# record.net
KiCad netlist of a schematic drawn in Altium Designer
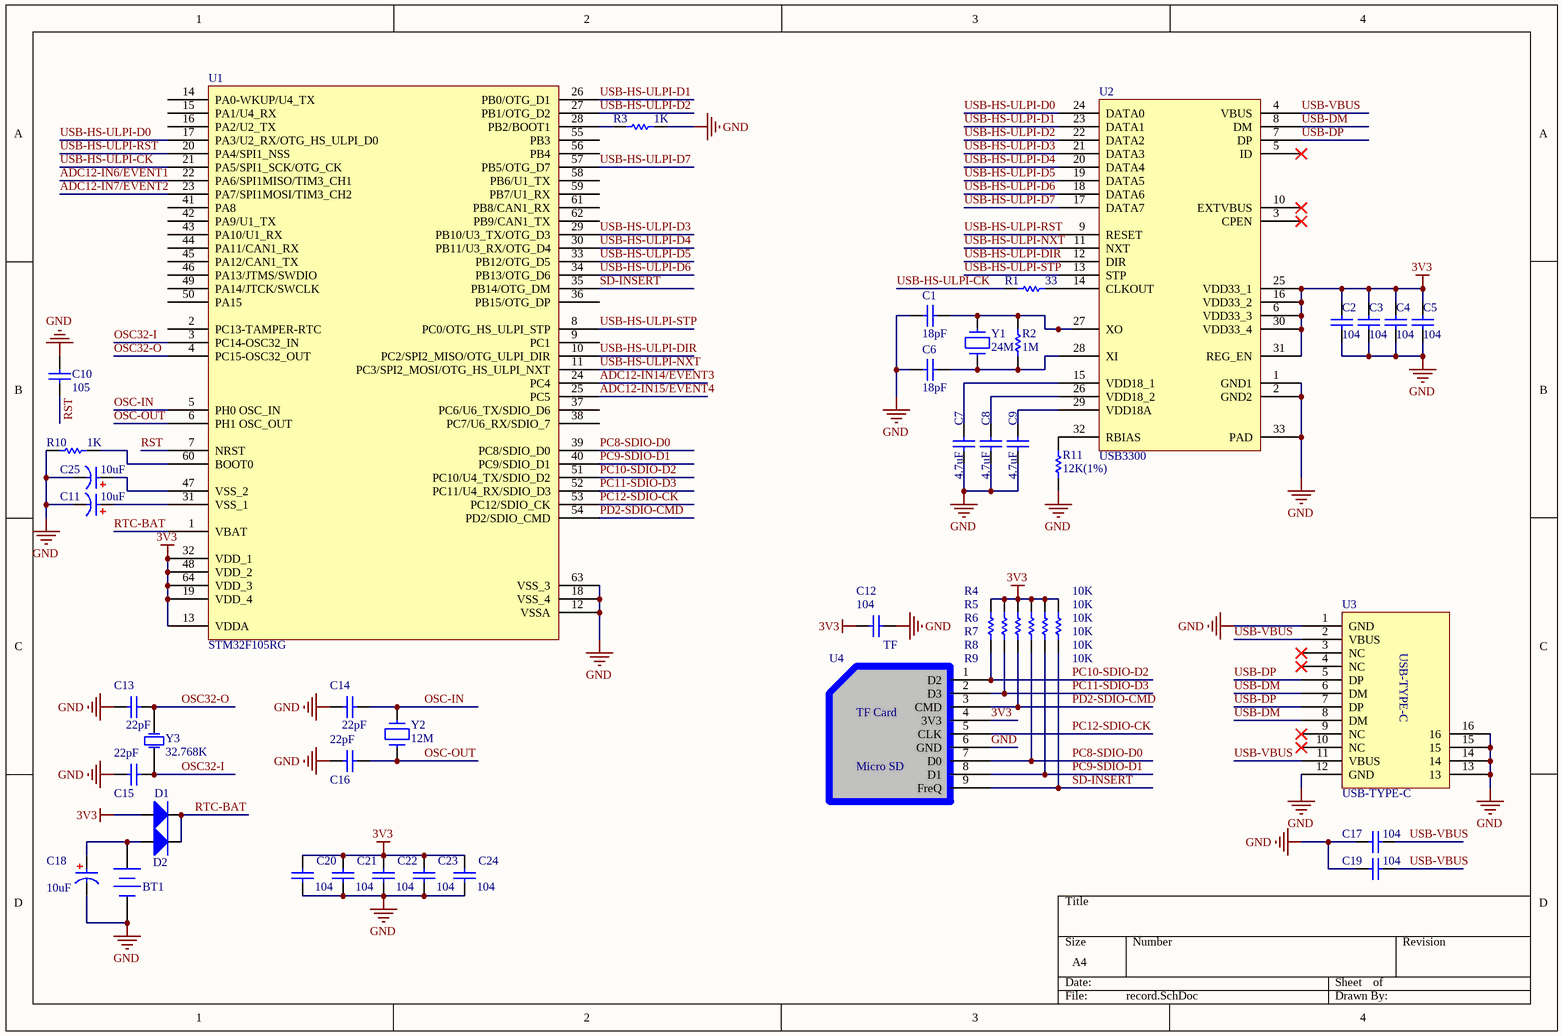
[diagram p0: record.SchDoc]

(export (version "E")
  (design (tool "Eeschema 10.0.6"))
  (components
    (comp (ref "BT1")
      (value "Battery")
      (footprint "BAT1")
      (description "Multicell Battery")
      (fields (field (name "PUBLISHER") "Altium Limited"))
      (libsource (lib "Miscellaneous Devices") (part "Battery"))
    )
    (comp (ref "C1")
      (value "C18pF")
      (footprint "0603R")
      (description "贴片电容")
      (fields (field (name "ALTIUM_UNNAMED_1") "18pF"))
      (libsource (lib "OKmeSchLibrary") (part "C22pF"))
    )
    (comp (ref "C2")
      (value "104")
      (footprint "0603C")
      (fields (field (name "ALTIUM_UNNAMED_1") "104"))
      (libsource (lib "OKmeSchLibrary") (part "C0.1uF"))
    )
    (comp (ref "C3")
      (value "104")
      (footprint "0603C")
      (fields (field (name "ALTIUM_UNNAMED_1") "104"))
      (libsource (lib "OKmeSchLibrary") (part "C0.1uF"))
    )
    (comp (ref "C4")
      (value "104")
      (footprint "0603C")
      (fields (field (name "ALTIUM_UNNAMED_1") "104"))
      (libsource (lib "OKmeSchLibrary") (part "C0.1uF"))
    )
    (comp (ref "C5")
      (value "104")
      (footprint "0603C")
      (fields (field (name "ALTIUM_UNNAMED_1") "104"))
      (libsource (lib "OKmeSchLibrary") (part "C0.1uF"))
    )
    (comp (ref "C6")
      (value "C18pF")
      (footprint "0603R")
      (description "贴片电容")
      (fields (field (name "ALTIUM_UNNAMED_1") "18pF"))
      (libsource (lib "OKmeSchLibrary") (part "C22pF"))
    )
    (comp (ref "C7")
      (value "C4.7uF")
      (footprint "0603R")
      (description "贴片电容")
      (fields (field (name "ALTIUM_UNNAMED_1") "4.7uF"))
      (libsource (lib "OKmeSchLibrary") (part "C22pF"))
    )
    (comp (ref "C8")
      (value "C4.7uF")
      (footprint "0603R")
      (description "贴片电容")
      (fields (field (name "ALTIUM_UNNAMED_1") "4.7uF"))
      (libsource (lib "OKmeSchLibrary") (part "C22pF"))
    )
    (comp (ref "C9")
      (value "C4.7uF")
      (footprint "0603R")
      (description "贴片电容")
      (fields (field (name "ALTIUM_UNNAMED_1") "4.7uF"))
      (libsource (lib "OKmeSchLibrary") (part "C22pF"))
    )
    (comp (ref "C10")
      (value "C1uF")
      (footprint "0603C")
      (fields (field (name "ALTIUM_UNNAMED_1") "105"))
      (libsource (lib "OKmeSchLibrary") (part "C0.1uF"))
    )
    (comp (ref "C11")
      (value "C10uF")
      (footprint "0603C")
      (fields (field (name "ALTIUM_UNNAMED_1") "10uF"))
      (libsource (lib "") (part "C10uF_1"))
    )
    (comp (ref "C12")
      (value "C0.1uF")
      (footprint "0603C")
      (fields (field (name "ALTIUM_UNNAMED_1") "104"))
      (libsource (lib "OKmeSchLibrary") (part "0603C"))
    )
    (comp (ref "C13")
      (value "C22pF")
      (footprint "0603R")
      (fields (field (name "ALTIUM_UNNAMED_1") "22pF"))
      (libsource (lib "OKmeSchLibrary") (part "C22pF"))
    )
    (comp (ref "C14")
      (value "C22pF")
      (footprint "0603R")
      (fields (field (name "ALTIUM_UNNAMED_1") "22pF"))
      (libsource (lib "OKmeSchLibrary") (part "C22pF"))
    )
    (comp (ref "C15")
      (value "C22pF")
      (footprint "0603R")
      (fields (field (name "ALTIUM_UNNAMED_1") "22pF"))
      (libsource (lib "OKmeSchLibrary") (part "C22pF"))
    )
    (comp (ref "C16")
      (value "C22pF")
      (footprint "0603R")
      (fields (field (name "ALTIUM_UNNAMED_1") "22pF"))
      (libsource (lib "OKmeSchLibrary") (part "C22pF"))
    )
    (comp (ref "C17")
      (value "104")
      (footprint "0603C")
      (fields (field (name "ALTIUM_UNNAMED_1") "104"))
      (libsource (lib "OKmeSchLibrary") (part "C0.1uF"))
    )
    (comp (ref "C18")
      (value "C10uF")
      (footprint "0603C")
      (fields (field (name "ALTIUM_UNNAMED_1") "10uF"))
      (libsource (lib "OKmeSchLibrary") (part "C10uF"))
    )
    (comp (ref "C19")
      (value "104")
      (footprint "0603C")
      (fields (field (name "ALTIUM_UNNAMED_1") "104"))
      (libsource (lib "OKmeSchLibrary") (part "C0.1uF"))
    )
    (comp (ref "C20")
      (value "104")
      (footprint "0603C")
      (fields (field (name "ALTIUM_UNNAMED_1") "104"))
      (libsource (lib "OKmeSchLibrary") (part "C0.1uF"))
    )
    (comp (ref "C21")
      (value "104")
      (footprint "0603C")
      (fields (field (name "ALTIUM_UNNAMED_1") "104"))
      (libsource (lib "OKmeSchLibrary") (part "C0.1uF"))
    )
    (comp (ref "C22")
      (value "104")
      (footprint "0603C")
      (fields (field (name "ALTIUM_UNNAMED_1") "104"))
      (libsource (lib "OKmeSchLibrary") (part "C0.1uF"))
    )
    (comp (ref "C23")
      (value "104")
      (footprint "0603C")
      (fields (field (name "ALTIUM_UNNAMED_1") "104"))
      (libsource (lib "OKmeSchLibrary") (part "C0.1uF"))
    )
    (comp (ref "C24")
      (value "104")
      (footprint "0603C")
      (fields (field (name "ALTIUM_UNNAMED_1") "104"))
      (libsource (lib "OKmeSchLibrary") (part "C0.1uF"))
    )
    (comp (ref "C25")
      (value "C10uF")
      (footprint "0603C")
      (fields (field (name "ALTIUM_UNNAMED_1") "10uF"))
      (libsource (lib "") (part "C10uF_1"))
    )
    (comp (ref "D1") (value "1N5822") (footprint "1206") (libsource (lib "OKmeSchLibrary") (part "1N5822")))
    (comp (ref "D2") (value "1N5822") (footprint "1206") (libsource (lib "OKmeSchLibrary") (part "1N5822")))
    (comp (ref "R1")
      (value "R33")
      (footprint "0603R")
      (fields (field (name "ALTIUM_UNNAMED_1") "33"))
      (libsource (lib "OKmeSchLibrary") (part "R22"))
    )
    (comp (ref "R2")
      (value "R1M")
      (footprint "0603R")
      (fields (field (name "ALTIUM_UNNAMED_1") "1M"))
      (libsource (lib "OKmeSchLibrary") (part "R1M"))
    )
    (comp (ref "R3")
      (value "R1K")
      (footprint "0603R")
      (fields (field (name "ALTIUM_UNNAMED_1") "1K"))
      (libsource (lib "OKmeSchLibrary") (part "R10K"))
    )
    (comp (ref "R4")
      (value "R10K")
      (footprint "0603R")
      (fields (field (name "ALTIUM_UNNAMED_1") "10K"))
      (libsource (lib "OKmeSchLibrary") (part "R10K"))
    )
    (comp (ref "R5")
      (value "R10K")
      (footprint "0603R")
      (fields (field (name "ALTIUM_UNNAMED_1") "10K"))
      (libsource (lib "OKmeSchLibrary") (part "R10K"))
    )
    (comp (ref "R6")
      (value "R10K")
      (footprint "0603R")
      (fields (field (name "ALTIUM_UNNAMED_1") "10K"))
      (libsource (lib "OKmeSchLibrary") (part "R10K"))
    )
    (comp (ref "R7")
      (value "R10K")
      (footprint "0603R")
      (fields (field (name "ALTIUM_UNNAMED_1") "10K"))
      (libsource (lib "OKmeSchLibrary") (part "R10K"))
    )
    (comp (ref "R8")
      (value "R10K")
      (footprint "0603R")
      (fields (field (name "ALTIUM_UNNAMED_1") "10K"))
      (libsource (lib "OKmeSchLibrary") (part "R10K"))
    )
    (comp (ref "R9")
      (value "R10K")
      (footprint "0603R")
      (fields (field (name "ALTIUM_UNNAMED_1") "10K"))
      (libsource (lib "OKmeSchLibrary") (part "R10K"))
    )
    (comp (ref "R10")
      (value "R1K")
      (footprint "0603R")
      (fields (field (name "ALTIUM_UNNAMED_1") "1K"))
      (libsource (lib "OKmeSchLibrary") (part "R10K"))
    )
    (comp (ref "R11")
      (value "R12K(1%)")
      (footprint "0603R")
      (fields (field (name "ALTIUM_UNNAMED_1") "12K(1%)"))
      (libsource (lib "OKmeSchLibrary") (part "R1M"))
    )
    (comp (ref "U1")
      (value "STM32F105RG")
      (footprint "LQFP64")
      (libsource (lib "OKmeSchLibrary") (part "STM32F405RG"))
    )
    (comp (ref "U2") (value "USB3300") (libsource (lib "OKmeSchLibrary") (part "USB3300")))
    (comp (ref "U3") (value "USB-TYPE-C") (libsource (lib "OKmeSchLibrary") (part "USB-TYPE-C")))
    (comp (ref "U4") (value "TF") (footprint "TF CARD") (libsource (lib "OKmeSchLibrary") (part "TF")))
    (comp (ref "Y1")
      (value "24M")
      (footprint "XTAL3225")
      (description "Crystal")
      (libsource (lib "*") (part "CRYSTAL"))
    )
    (comp (ref "Y2")
      (value "12M")
      (footprint "XTAL3225")
      (description "Crystal")
      (libsource (lib "*") (part "CRYSTAL"))
    )
    (comp (ref "Y3")
      (value "Y32.768K-3216")
      (footprint "CRY3215-2P")
      (fields (field (name "ALTIUM_UNNAMED_1") "32.768K"))
      (libsource (lib "OKmeSchLibrary") (part "Y32.768K"))
    )
  )
  (nets
    (net (code "1") (name "/ADC12-IN6{slash}EVENT1") (class "Default")
      (node (ref "U1") (pin "22") (pinfunction "PA6/SPI1MISO/TIM3_CH1_22") (pintype "passive"))
    )
    (net (code "2") (name "/ADC12-IN7{slash}EVENT2") (class "Default")
      (node (ref "U1") (pin "23") (pinfunction "PA7/SPI1MOSI/TIM3_CH2_23") (pintype "passive"))
    )
    (net (code "3") (name "/ADC12-IN14{slash}EVENT3") (class "Default")
      (node (ref "U1") (pin "24") (pinfunction "PC4_24") (pintype "passive"))
    )
    (net (code "4") (name "/ADC12-IN15{slash}EVENT4") (class "Default")
      (node (ref "U1") (pin "25") (pinfunction "PC5_25") (pintype "passive"))
    )
    (net (code "5") (name "/OSC-IN") (class "Default")
      (node (ref "C14") (pin "2") (pinfunction "2_2") (pintype "passive"))
      (node (ref "U1") (pin "5") (pinfunction "PH0_OSC_IN_5") (pintype "passive"))
      (node (ref "Y2") (pin "3") (pinfunction "3_3") (pintype "passive"))
    )
    (net (code "6") (name "/OSC-OUT") (class "Default")
      (node (ref "C16") (pin "2") (pinfunction "2_2") (pintype "passive"))
      (node (ref "U1") (pin "6") (pinfunction "PH1_OSC_OUT_6") (pintype "passive"))
      (node (ref "Y2") (pin "1") (pinfunction "1_1") (pintype "passive"))
    )
    (net (code "7") (name "/OSC32-I") (class "Default")
      (node (ref "C15") (pin "2") (pinfunction "2_2") (pintype "passive"))
      (node (ref "U1") (pin "3") (pinfunction "PC14-OSC32_IN_3") (pintype "passive"))
      (node (ref "Y3") (pin "1") (pinfunction "OSC1_1") (pintype "passive"))
    )
    (net (code "8") (name "/OSC32-O") (class "Default")
      (node (ref "C13") (pin "2") (pinfunction "2_2") (pintype "passive"))
      (node (ref "U1") (pin "4") (pinfunction "PC15-OSC32_OUT_4") (pintype "passive"))
      (node (ref "Y3") (pin "2") (pinfunction "OSC2_2") (pintype "passive"))
    )
    (net (code "9") (name "/PC8-SDIO-D0") (class "Default")
      (node (ref "R7") (pin "1") (pinfunction "1_1") (pintype "passive"))
      (node (ref "U1") (pin "39") (pinfunction "PC8/SDIO_D0_39") (pintype "passive"))
      (node (ref "U4") (pin "7") (pinfunction "D0_7") (pintype "passive"))
    )
    (net (code "10") (name "/PC9-SDIO-D1") (class "Default")
      (node (ref "R8") (pin "1") (pinfunction "1_1") (pintype "passive"))
      (node (ref "U1") (pin "40") (pinfunction "PC9/SDIO_D1_40") (pintype "passive"))
      (node (ref "U4") (pin "8") (pinfunction "D1_8") (pintype "passive"))
    )
    (net (code "11") (name "/PC10-SDIO-D2") (class "Default")
      (node (ref "R4") (pin "1") (pinfunction "1_1") (pintype "passive"))
      (node (ref "U1") (pin "51") (pinfunction "PC10/U4_TX/SDIO_D2_51") (pintype "passive"))
      (node (ref "U4") (pin "1") (pinfunction "D2_1") (pintype "passive"))
    )
    (net (code "12") (name "/PC11-SDIO-D3") (class "Default")
      (node (ref "R5") (pin "1") (pinfunction "1_1") (pintype "passive"))
      (node (ref "U1") (pin "52") (pinfunction "PC11/U4_RX/SDIO_D3_52") (pintype "passive"))
      (node (ref "U4") (pin "2") (pinfunction "D3_2") (pintype "passive"))
    )
    (net (code "13") (name "/PC12-SDIO-CK") (class "Default")
      (node (ref "U1") (pin "53") (pinfunction "PC12/SDIO_CK_53") (pintype "passive"))
      (node (ref "U4") (pin "5") (pinfunction "CLK_5") (pintype "passive"))
    )
    (net (code "14") (name "/PD2-SDIO-CMD") (class "Default")
      (node (ref "R6") (pin "1") (pinfunction "1_1") (pintype "passive"))
      (node (ref "U1") (pin "54") (pinfunction "PD2/SDIO_CMD_54") (pintype "passive"))
      (node (ref "U4") (pin "3") (pinfunction "CMD_3") (pintype "passive"))
    )
    (net (code "15") (name "/RST") (class "Default")
      (node (ref "C10") (pin "1") (pinfunction "1_1") (pintype "passive"))
      (node (ref "U1") (pin "7") (pinfunction "NRST_7") (pintype "passive"))
    )
    (net (code "16") (name "/RTC-BAT") (class "Default")
      (node (ref "D1") (pin "2") (pinfunction "K_2") (pintype "passive"))
      (node (ref "D2") (pin "2") (pinfunction "K_2") (pintype "passive"))
      (node (ref "U1") (pin "1") (pinfunction "VBAT_1") (pintype "passive"))
    )
    (net (code "17") (name "/SD-INSERT") (class "Default")
      (node (ref "R9") (pin "1") (pinfunction "1_1") (pintype "passive"))
      (node (ref "U1") (pin "35") (pinfunction "PB14/OTG_DM_35") (pintype "passive"))
      (node (ref "U4") (pin "9") (pinfunction "FreQ_9") (pintype "passive"))
    )
    (net (code "18") (name "/USB-DM") (class "Default")
      (node (ref "U2") (pin "8") (pinfunction "DM_8") (pintype "passive"))
      (node (ref "U3") (pin "6") (pinfunction "DM_6") (pintype "passive"))
      (node (ref "U3") (pin "8") (pinfunction "DM_8") (pintype "passive"))
    )
    (net (code "19") (name "/USB-DP") (class "Default")
      (node (ref "U2") (pin "7") (pinfunction "DP_7") (pintype "passive"))
      (node (ref "U3") (pin "5") (pinfunction "DP_5") (pintype "passive"))
      (node (ref "U3") (pin "7") (pinfunction "DP_7") (pintype "passive"))
    )
    (net (code "20") (name "/USB-HS-ULPI-CK") (class "Default")
      (node (ref "R1") (pin "1") (pinfunction "1_1") (pintype "passive"))
      (node (ref "U1") (pin "21") (pinfunction "PA5/SPI1_SCK/OTG_CK_21") (pintype "passive"))
    )
    (net (code "21") (name "/USB-HS-ULPI-D0") (class "Default")
      (node (ref "U1") (pin "17") (pinfunction "PA3/U2_RX/OTG_HS_ULPI_D0_17") (pintype "passive"))
      (node (ref "U2") (pin "24") (pinfunction "DATA0_24") (pintype "passive"))
    )
    (net (code "22") (name "/USB-HS-ULPI-D1") (class "Default")
      (node (ref "U1") (pin "26") (pinfunction "PB0/OTG_D1_26") (pintype "passive"))
      (node (ref "U2") (pin "23") (pinfunction "DATA1_23") (pintype "passive"))
    )
    (net (code "23") (name "/USB-HS-ULPI-D2") (class "Default")
      (node (ref "U1") (pin "27") (pinfunction "PB1/OTG_D2_27") (pintype "passive"))
      (node (ref "U2") (pin "22") (pinfunction "DATA2_22") (pintype "passive"))
    )
    (net (code "24") (name "/USB-HS-ULPI-D3") (class "Default")
      (node (ref "U1") (pin "29") (pinfunction "PB10/U3_TX/OTG_D3_29") (pintype "passive"))
      (node (ref "U2") (pin "21") (pinfunction "DATA3_21") (pintype "passive"))
    )
    (net (code "25") (name "/USB-HS-ULPI-D4") (class "Default")
      (node (ref "U1") (pin "30") (pinfunction "PB11/U3_RX/OTG_D4_30") (pintype "passive"))
      (node (ref "U2") (pin "20") (pinfunction "DATA4_20") (pintype "passive"))
    )
    (net (code "26") (name "/USB-HS-ULPI-D5") (class "Default")
      (node (ref "U1") (pin "33") (pinfunction "PB12/OTG_D5_33") (pintype "passive"))
      (node (ref "U2") (pin "19") (pinfunction "DATA5_19") (pintype "passive"))
    )
    (net (code "27") (name "/USB-HS-ULPI-D6") (class "Default")
      (node (ref "U1") (pin "34") (pinfunction "PB13/OTG_D6_34") (pintype "passive"))
      (node (ref "U2") (pin "18") (pinfunction "DATA6_18") (pintype "passive"))
    )
    (net (code "28") (name "/USB-HS-ULPI-D7") (class "Default")
      (node (ref "U1") (pin "57") (pinfunction "PB5/OTG_D7_57") (pintype "passive"))
      (node (ref "U2") (pin "17") (pinfunction "DATA7_17") (pintype "passive"))
    )
    (net (code "29") (name "/USB-HS-ULPI-DIR") (class "Default")
      (node (ref "U1") (pin "10") (pinfunction "PC2/SPI2_MISO/OTG_ULPI_DIR_10") (pintype "passive"))
      (node (ref "U2") (pin "12") (pinfunction "DIR_12") (pintype "passive"))
    )
    (net (code "30") (name "/USB-HS-ULPI-NXT") (class "Default")
      (node (ref "U1") (pin "11") (pinfunction "PC3/SPI2_MOSI/OTG_HS_ULPI_NXT_11") (pintype "passive"))
      (node (ref "U2") (pin "11") (pinfunction "NXT_11") (pintype "passive"))
    )
    (net (code "31") (name "/USB-HS-ULPI-RST") (class "Default")
      (node (ref "U1") (pin "20") (pinfunction "PA4/SPI1_NSS_20") (pintype "passive"))
      (node (ref "U2") (pin "9") (pinfunction "RESET_9") (pintype "passive"))
    )
    (net (code "32") (name "/USB-HS-ULPI-STP") (class "Default")
      (node (ref "U1") (pin "8") (pinfunction "PC0/OTG_HS_ULPI_STP_8") (pintype "passive"))
      (node (ref "U2") (pin "13") (pinfunction "STP_13") (pintype "passive"))
    )
    (net (code "33") (name "/USB-VBUS") (class "Default")
      (node (ref "C17") (pin "2") (pinfunction "2_2") (pintype "passive"))
      (node (ref "C19") (pin "2") (pinfunction "2_2") (pintype "passive"))
      (node (ref "U2") (pin "4") (pinfunction "VBUS_4") (pintype "passive"))
      (node (ref "U3") (pin "11") (pinfunction "VBUS_11") (pintype "passive"))
      (node (ref "U3") (pin "2") (pinfunction "VBUS_2") (pintype "passive"))
    )
    (net (code "34") (name "3V3") (class "Default")
      (node (ref "C12") (pin "2") (pinfunction "2_2") (pintype "passive"))
      (node (ref "C2") (pin "2") (pinfunction "2_2") (pintype "passive"))
      (node (ref "C20") (pin "2") (pinfunction "2_2") (pintype "passive"))
      (node (ref "C21") (pin "2") (pinfunction "2_2") (pintype "passive"))
      (node (ref "C22") (pin "2") (pinfunction "2_2") (pintype "passive"))
      (node (ref "C23") (pin "2") (pinfunction "2_2") (pintype "passive"))
      (node (ref "C24") (pin "2") (pinfunction "2_2") (pintype "passive"))
      (node (ref "C3") (pin "2") (pinfunction "2_2") (pintype "passive"))
      (node (ref "C4") (pin "2") (pinfunction "2_2") (pintype "passive"))
      (node (ref "C5") (pin "2") (pinfunction "2_2") (pintype "passive"))
      (node (ref "D1") (pin "1") (pinfunction "A_1") (pintype "passive"))
      (node (ref "R4") (pin "2") (pinfunction "2_2") (pintype "passive"))
      (node (ref "R5") (pin "2") (pinfunction "2_2") (pintype "passive"))
      (node (ref "R6") (pin "2") (pinfunction "2_2") (pintype "passive"))
      (node (ref "R7") (pin "2") (pinfunction "2_2") (pintype "passive"))
      (node (ref "R8") (pin "2") (pinfunction "2_2") (pintype "passive"))
      (node (ref "R9") (pin "2") (pinfunction "2_2") (pintype "passive"))
      (node (ref "U1") (pin "13") (pinfunction "VDDA_13") (pintype "passive"))
      (node (ref "U1") (pin "19") (pinfunction "VDD_4_19") (pintype "passive"))
      (node (ref "U1") (pin "32") (pinfunction "VDD_1_32") (pintype "passive"))
      (node (ref "U1") (pin "48") (pinfunction "VDD_2_48") (pintype "passive"))
      (node (ref "U1") (pin "64") (pinfunction "VDD_3_64") (pintype "passive"))
      (node (ref "U2") (pin "16") (pinfunction "VDD33_2_16") (pintype "passive"))
      (node (ref "U2") (pin "25") (pinfunction "VDD33_1_25") (pintype "passive"))
      (node (ref "U2") (pin "30") (pinfunction "VDD33_4_30") (pintype "passive"))
      (node (ref "U2") (pin "31") (pinfunction "REG_EN_31") (pintype "passive"))
      (node (ref "U2") (pin "6") (pinfunction "VDD33_3_6") (pintype "passive"))
      (node (ref "U4") (pin "4") (pinfunction "3V3_4") (pintype "passive"))
    )
    (net (code "35") (name "GND") (class "Default")
      (node (ref "BT1") (pin "2") (pinfunction "-_2") (pintype "passive"))
      (node (ref "C1") (pin "1") (pinfunction "1_1") (pintype "passive"))
      (node (ref "C10") (pin "2") (pinfunction "2_2") (pintype "passive"))
      (node (ref "C11") (pin "2") (pinfunction "2_2") (pintype "passive"))
      (node (ref "C12") (pin "1") (pinfunction "1_1") (pintype "passive"))
      (node (ref "C13") (pin "1") (pinfunction "1_1") (pintype "passive"))
      (node (ref "C14") (pin "1") (pinfunction "1_1") (pintype "passive"))
      (node (ref "C15") (pin "1") (pinfunction "1_1") (pintype "passive"))
      (node (ref "C16") (pin "1") (pinfunction "1_1") (pintype "passive"))
      (node (ref "C17") (pin "1") (pinfunction "1_1") (pintype "passive"))
      (node (ref "C18") (pin "2") (pinfunction "2_2") (pintype "passive"))
      (node (ref "C19") (pin "1") (pinfunction "1_1") (pintype "passive"))
      (node (ref "C2") (pin "1") (pinfunction "1_1") (pintype "passive"))
      (node (ref "C20") (pin "1") (pinfunction "1_1") (pintype "passive"))
      (node (ref "C21") (pin "1") (pinfunction "1_1") (pintype "passive"))
      (node (ref "C22") (pin "1") (pinfunction "1_1") (pintype "passive"))
      (node (ref "C23") (pin "1") (pinfunction "1_1") (pintype "passive"))
      (node (ref "C24") (pin "1") (pinfunction "1_1") (pintype "passive"))
      (node (ref "C25") (pin "2") (pinfunction "2_2") (pintype "passive"))
      (node (ref "C3") (pin "1") (pinfunction "1_1") (pintype "passive"))
      (node (ref "C4") (pin "1") (pinfunction "1_1") (pintype "passive"))
      (node (ref "C5") (pin "1") (pinfunction "1_1") (pintype "passive"))
      (node (ref "C6") (pin "1") (pinfunction "1_1") (pintype "passive"))
      (node (ref "C7") (pin "1") (pinfunction "1_1") (pintype "passive"))
      (node (ref "C8") (pin "1") (pinfunction "1_1") (pintype "passive"))
      (node (ref "C9") (pin "1") (pinfunction "1_1") (pintype "passive"))
      (node (ref "R10") (pin "1") (pinfunction "1_1") (pintype "passive"))
      (node (ref "R11") (pin "1") (pinfunction "1_1") (pintype "passive"))
      (node (ref "R3") (pin "2") (pinfunction "2_2") (pintype "passive"))
      (node (ref "U1") (pin "12") (pinfunction "VSSA_12") (pintype "passive"))
      (node (ref "U1") (pin "18") (pinfunction "VSS_4_18") (pintype "passive"))
      (node (ref "U1") (pin "63") (pinfunction "VSS_3_63") (pintype "passive"))
      (node (ref "U2") (pin "1") (pinfunction "GND1_1") (pintype "passive"))
      (node (ref "U2") (pin "2") (pinfunction "GND2_2") (pintype "passive"))
      (node (ref "U2") (pin "33") (pinfunction "PAD_33") (pintype "passive"))
      (node (ref "U3") (pin "1") (pinfunction "GND_1") (pintype "passive"))
      (node (ref "U3") (pin "12") (pinfunction "GND_12") (pintype "passive"))
      (node (ref "U3") (pin "13") (pinfunction "13_13") (pintype "passive"))
      (node (ref "U3") (pin "14") (pinfunction "14_14") (pintype "passive"))
      (node (ref "U3") (pin "15") (pinfunction "15_15") (pintype "passive"))
      (node (ref "U3") (pin "16") (pinfunction "16_16") (pintype "passive"))
      (node (ref "U4") (pin "6") (pinfunction "GND_6") (pintype "passive"))
    )
    (net (code "36") (name "Net-(BT1-+)") (class "Default")
      (node (ref "BT1") (pin "1") (pinfunction "+_1") (pintype "passive"))
      (node (ref "C18") (pin "1") (pinfunction "1_1") (pintype "passive"))
      (node (ref "D2") (pin "1") (pinfunction "A_1") (pintype "passive"))
    )
    (net (code "37") (name "Net-(U1-BOOT0)") (class "Default")
      (node (ref "R10") (pin "2") (pinfunction "2_2") (pintype "passive"))
      (node (ref "U1") (pin "60") (pinfunction "BOOT0_60") (pintype "passive"))
    )
    (net (code "38") (name "Net-(U1-PB2{slash}BOOT1)") (class "Default")
      (node (ref "R3") (pin "1") (pinfunction "1_1") (pintype "passive"))
      (node (ref "U1") (pin "28") (pinfunction "PB2/BOOT1_28") (pintype "passive"))
    )
    (net (code "39") (name "Net-(U1-VSS_1)") (class "Default")
      (node (ref "C11") (pin "1") (pinfunction "1_1") (pintype "passive"))
      (node (ref "U1") (pin "31") (pinfunction "VSS_1_31") (pintype "passive"))
    )
    (net (code "40") (name "Net-(U1-VSS_2)") (class "Default")
      (node (ref "C25") (pin "1") (pinfunction "1_1") (pintype "passive"))
      (node (ref "U1") (pin "47") (pinfunction "VSS_2_47") (pintype "passive"))
    )
    (net (code "41") (name "Net-(U2-CLKOUT)") (class "Default")
      (node (ref "R1") (pin "2") (pinfunction "2_2") (pintype "passive"))
      (node (ref "U2") (pin "14") (pinfunction "CLKOUT_14") (pintype "passive"))
    )
    (net (code "42") (name "Net-(U2-RBIAS)") (class "Default")
      (node (ref "R11") (pin "2") (pinfunction "2_2") (pintype "passive"))
      (node (ref "U2") (pin "32") (pinfunction "RBIAS_32") (pintype "passive"))
    )
    (net (code "43") (name "Net-(U2-VDD18A)") (class "Default")
      (node (ref "C9") (pin "2") (pinfunction "2_2") (pintype "passive"))
      (node (ref "U2") (pin "29") (pinfunction "VDD18A_29") (pintype "passive"))
    )
    (net (code "44") (name "Net-(U2-VDD18_1)") (class "Default")
      (node (ref "C7") (pin "2") (pinfunction "2_2") (pintype "passive"))
      (node (ref "U2") (pin "15") (pinfunction "VDD18_1_15") (pintype "passive"))
    )
    (net (code "45") (name "Net-(U2-VDD18_2)") (class "Default")
      (node (ref "C8") (pin "2") (pinfunction "2_2") (pintype "passive"))
      (node (ref "U2") (pin "26") (pinfunction "VDD18_2_26") (pintype "passive"))
    )
    (net (code "46") (name "Net-(U2-XI)") (class "Default")
      (node (ref "C6") (pin "2") (pinfunction "2_2") (pintype "passive"))
      (node (ref "R2") (pin "1") (pinfunction "1_1") (pintype "passive"))
      (node (ref "U2") (pin "28") (pinfunction "XI_28") (pintype "passive"))
      (node (ref "Y1") (pin "1") (pinfunction "1_1") (pintype "passive"))
    )
    (net (code "47") (name "Net-(U2-XO)") (class "Default")
      (node (ref "C1") (pin "2") (pinfunction "2_2") (pintype "passive"))
      (node (ref "R2") (pin "2") (pinfunction "2_2") (pintype "passive"))
      (node (ref "U2") (pin "27") (pinfunction "XO_27") (pintype "passive"))
      (node (ref "Y1") (pin "3") (pinfunction "3_3") (pintype "passive"))
    )
    (net (code "48") (name "unconnected-(U1-PA0-WKUP{slash}U4_TX-Pad14)") (class "Default")
      (node (ref "U1") (pin "14") (pinfunction "PA0-WKUP/U4_TX_14") (pintype "passive"))
    )
    (net (code "49") (name "unconnected-(U1-PA1{slash}U4_RX-Pad15)") (class "Default")
      (node (ref "U1") (pin "15") (pinfunction "PA1/U4_RX_15") (pintype "passive"))
    )
    (net (code "50") (name "unconnected-(U1-PA2{slash}U2_TX-Pad16)") (class "Default")
      (node (ref "U1") (pin "16") (pinfunction "PA2/U2_TX_16") (pintype "passive"))
    )
    (net (code "51") (name "unconnected-(U1-PA8-Pad41)") (class "Default")
      (node (ref "U1") (pin "41") (pinfunction "PA8_41") (pintype "passive"))
    )
    (net (code "52") (name "unconnected-(U1-PA9{slash}U1_TX-Pad42)") (class "Default")
      (node (ref "U1") (pin "42") (pinfunction "PA9/U1_TX_42") (pintype "passive"))
    )
    (net (code "53") (name "unconnected-(U1-PA10{slash}U1_RX-Pad43)") (class "Default")
      (node (ref "U1") (pin "43") (pinfunction "PA10/U1_RX_43") (pintype "passive"))
    )
    (net (code "54") (name "unconnected-(U1-PA11{slash}CAN1_RX-Pad44)") (class "Default")
      (node (ref "U1") (pin "44") (pinfunction "PA11/CAN1_RX_44") (pintype "passive"))
    )
    (net (code "55") (name "unconnected-(U1-PA12{slash}CAN1_TX-Pad45)") (class "Default")
      (node (ref "U1") (pin "45") (pinfunction "PA12/CAN1_TX_45") (pintype "passive"))
    )
    (net (code "56") (name "unconnected-(U1-PA13{slash}JTMS{slash}SWDIO-Pad46)") (class "Default")
      (node (ref "U1") (pin "46") (pinfunction "PA13/JTMS/SWDIO_46") (pintype "passive"))
    )
    (net (code "57") (name "unconnected-(U1-PA14{slash}JTCK{slash}SWCLK-Pad49)") (class "Default")
      (node (ref "U1") (pin "49") (pinfunction "PA14/JTCK/SWCLK_49") (pintype "passive"))
    )
    (net (code "58") (name "unconnected-(U1-PA15-Pad50)") (class "Default")
      (node (ref "U1") (pin "50") (pinfunction "PA15_50") (pintype "passive"))
    )
    (net (code "59") (name "unconnected-(U1-PB3-Pad55)") (class "Default")
      (node (ref "U1") (pin "55") (pinfunction "PB3_55") (pintype "passive"))
    )
    (net (code "60") (name "unconnected-(U1-PB4-Pad56)") (class "Default")
      (node (ref "U1") (pin "56") (pinfunction "PB4_56") (pintype "passive"))
    )
    (net (code "61") (name "unconnected-(U1-PB6{slash}U1_TX-Pad58)") (class "Default")
      (node (ref "U1") (pin "58") (pinfunction "PB6/U1_TX_58") (pintype "passive"))
    )
    (net (code "62") (name "unconnected-(U1-PB7{slash}U1_RX-Pad59)") (class "Default")
      (node (ref "U1") (pin "59") (pinfunction "PB7/U1_RX_59") (pintype "passive"))
    )
    (net (code "63") (name "unconnected-(U1-PB8{slash}CAN1_RX-Pad61)") (class "Default")
      (node (ref "U1") (pin "61") (pinfunction "PB8/CAN1_RX_61") (pintype "passive"))
    )
    (net (code "64") (name "unconnected-(U1-PB9{slash}CAN1_TX-Pad62)") (class "Default")
      (node (ref "U1") (pin "62") (pinfunction "PB9/CAN1_TX_62") (pintype "passive"))
    )
    (net (code "65") (name "unconnected-(U1-PB15{slash}OTG_DP-Pad36)") (class "Default")
      (node (ref "U1") (pin "36") (pinfunction "PB15/OTG_DP_36") (pintype "passive"))
    )
    (net (code "66") (name "unconnected-(U1-PC1-Pad9)") (class "Default")
      (node (ref "U1") (pin "9") (pinfunction "PC1_9") (pintype "passive"))
    )
    (net (code "67") (name "unconnected-(U1-PC6{slash}U6_TX{slash}SDIO_D6-Pad37)") (class "Default")
      (node (ref "U1") (pin "37") (pinfunction "PC6/U6_TX/SDIO_D6_37") (pintype "passive"))
    )
    (net (code "68") (name "unconnected-(U1-PC7{slash}U6_RX{slash}SDIO_7-Pad38)") (class "Default")
      (node (ref "U1") (pin "38") (pinfunction "PC7/U6_RX/SDIO_7_38") (pintype "passive"))
    )
    (net (code "69") (name "unconnected-(U1-PC13-TAMPER-RTC-Pad2)") (class "Default")
      (node (ref "U1") (pin "2") (pinfunction "PC13-TAMPER-RTC_2") (pintype "passive"))
    )
    (net (code "70") (name "unconnected-(U2-CPEN-Pad3)") (class "Default")
      (node (ref "U2") (pin "3") (pinfunction "CPEN_3") (pintype "passive+no_connect"))
    )
    (net (code "71") (name "unconnected-(U2-EXTVBUS-Pad10)") (class "Default")
      (node (ref "U2") (pin "10") (pinfunction "EXTVBUS_10") (pintype "passive+no_connect"))
    )
    (net (code "72") (name "unconnected-(U2-ID-Pad5)") (class "Default")
      (node (ref "U2") (pin "5") (pinfunction "ID_5") (pintype "passive+no_connect"))
    )
    (net (code "73") (name "unconnected-(U3-NC-Pad3)") (class "Default")
      (node (ref "U3") (pin "3") (pinfunction "NC_3") (pintype "passive+no_connect"))
    )
    (net (code "74") (name "unconnected-(U3-NC-Pad4)") (class "Default")
      (node (ref "U3") (pin "4") (pinfunction "NC_4") (pintype "passive+no_connect"))
    )
    (net (code "75") (name "unconnected-(U3-NC-Pad9)") (class "Default")
      (node (ref "U3") (pin "9") (pinfunction "NC_9") (pintype "passive+no_connect"))
    )
    (net (code "76") (name "unconnected-(U3-NC-Pad10)") (class "Default")
      (node (ref "U3") (pin "10") (pinfunction "NC_10") (pintype "passive+no_connect"))
    )
  )
)
